# PSU.net
KiCad netlist of a schematic drawn in EAGLE
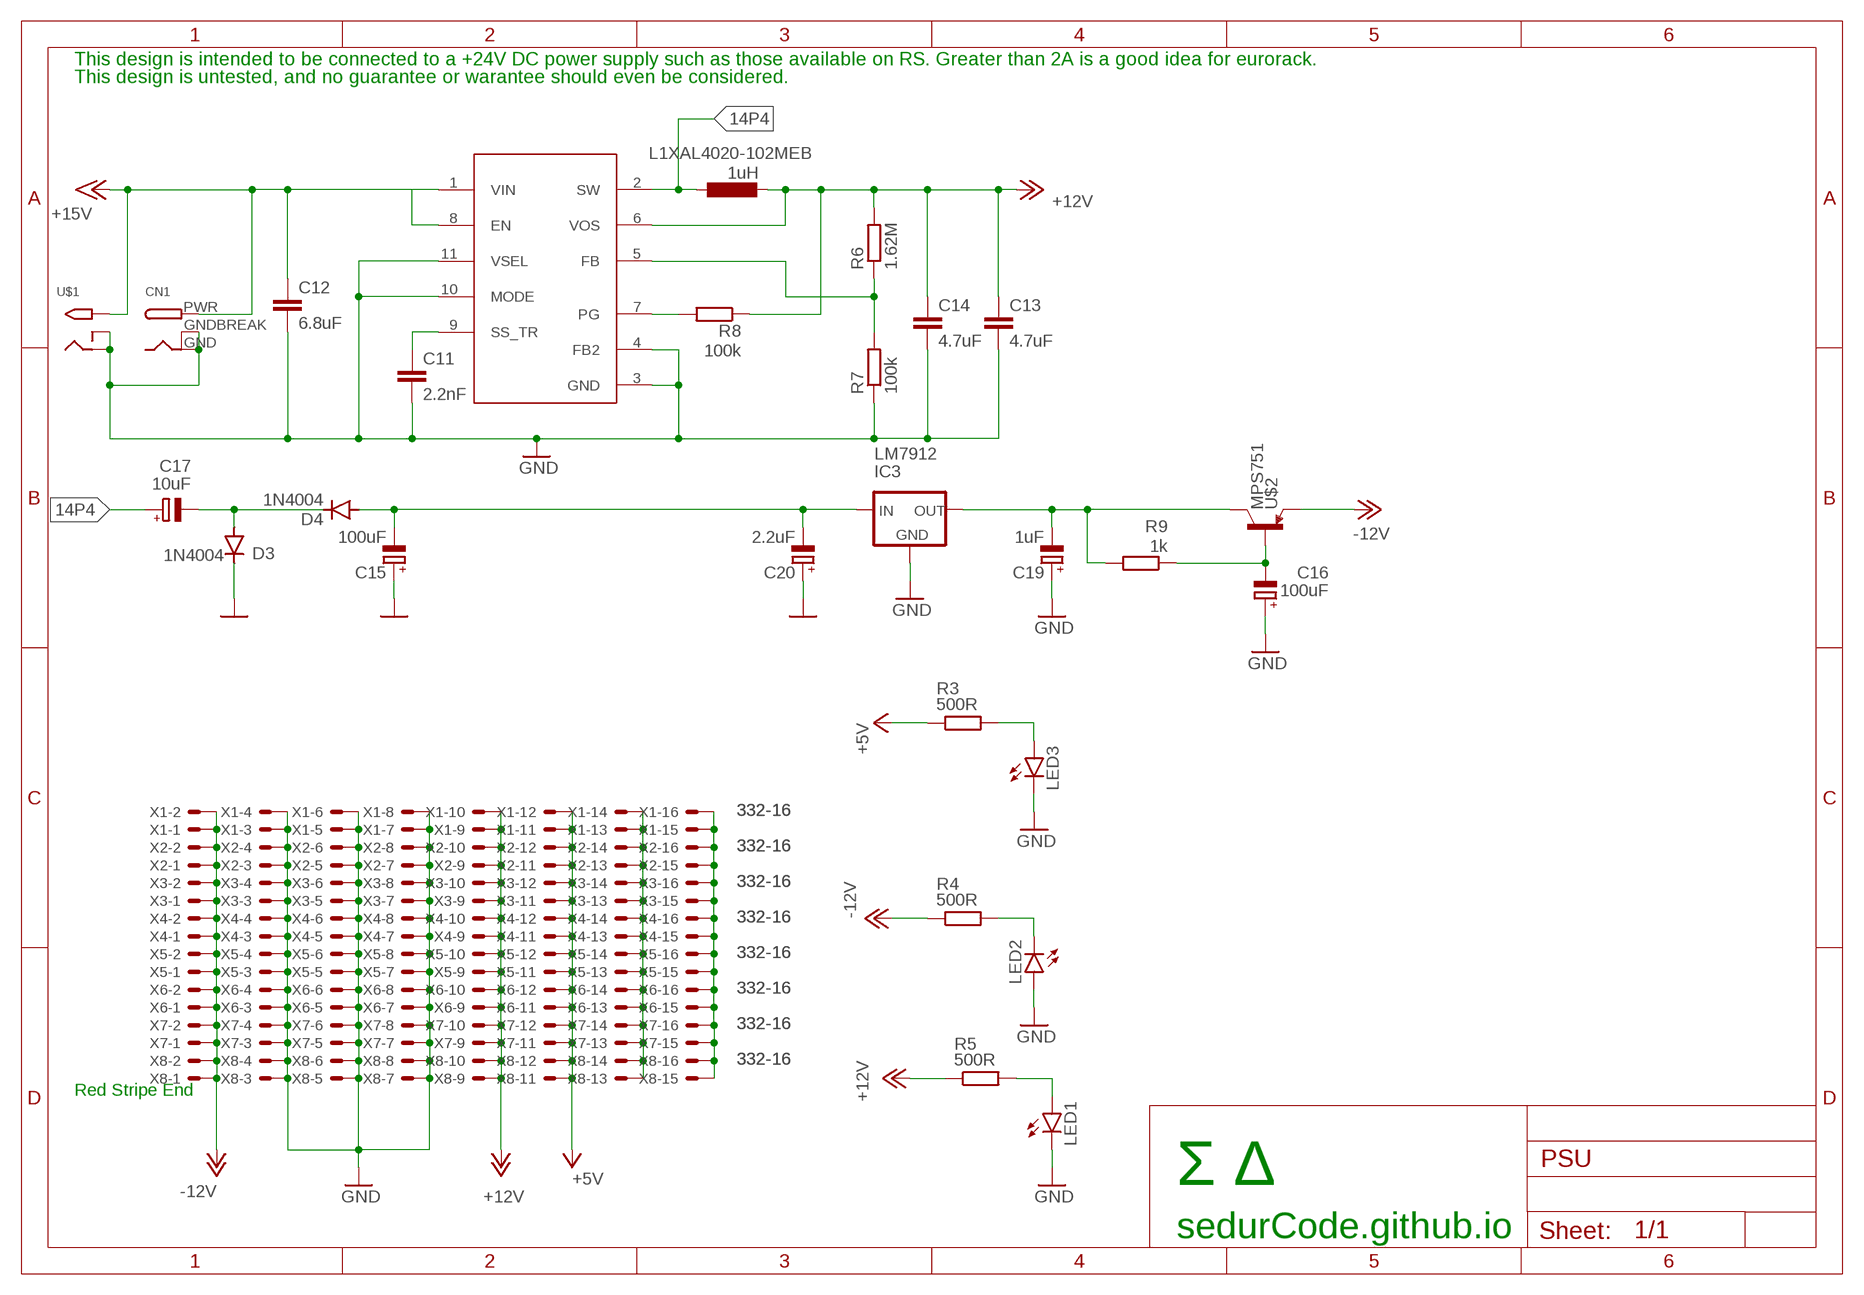
[diagram p0: schematic, sheet 1]

(export (version "E")
  (design (tool "Eeschema 10.0.6"))
  (components
    (comp (ref "C11")
      (value "2.2nF")
      (footprint "eagle-import:C0805")
      (libsource (lib "eagle-import") (part "C-EUC0805"))
    )
    (comp (ref "C12")
      (value "6.8uF")
      (footprint "eagle-import:C0805")
      (libsource (lib "eagle-import") (part "C-EUC0805"))
    )
    (comp (ref "C13")
      (value "4.7uF")
      (footprint "eagle-import:C0805")
      (libsource (lib "eagle-import") (part "C-EUC0805"))
    )
    (comp (ref "C14")
      (value "4.7uF")
      (footprint "eagle-import:C0805")
      (libsource (lib "eagle-import") (part "C-EUC0805"))
    )
    (comp (ref "C15")
      (value "100uF")
      (footprint "eagle-import:PANASONIC_B")
      (libsource (lib "eagle-import") (part "CPOL-EUB"))
    )
    (comp (ref "C16")
      (value "100uF")
      (footprint "eagle-import:PANASONIC_B")
      (libsource (lib "eagle-import") (part "CPOL-EUB"))
    )
    (comp (ref "C17")
      (value "10uF")
      (footprint "eagle-import:PANASONIC_B")
      (libsource (lib "eagle-import") (part "CPOL-EUB"))
    )
    (comp (ref "C19")
      (value "1uF")
      (footprint "eagle-import:PANASONIC_B")
      (libsource (lib "eagle-import") (part "CPOL-EUB"))
    )
    (comp (ref "C20")
      (value "2.2uF")
      (footprint "eagle-import:PANASONIC_B")
      (libsource (lib "eagle-import") (part "CPOL-EUB"))
    )
    (comp (ref "CN1")
      (value "DCBARRELPTH")
      (footprint "eagle-import:DCJACK_2MM_PTH")
      (fields (field (name "SPICEPREFIX") "X"))
      (libsource (lib "eagle-import") (part "DCBARRELPTH"))
    )
    (comp (ref "D3")
      (value "1N4004")
      (footprint "eagle-import:DO41-10")
      (libsource (lib "eagle-import") (part "1N4004"))
    )
    (comp (ref "D4")
      (value "1N4004")
      (footprint "eagle-import:DO41-10")
      (libsource (lib "eagle-import") (part "1N4004"))
    )
    (comp (ref "IC3")
      (value "LM7912")
      (footprint "eagle-import:79XXL")
      (fields (field (name "SPICEPREFIX") "J"))
      (libsource (lib "eagle-import") (part "79XXL"))
    )
    (comp (ref "L1XAL4020-102MEB")
      (value "1uH")
      (footprint "eagle-import:L5038P")
      (libsource (lib "eagle-import") (part "L-EUL5038P"))
    )
    (comp (ref "LED1")
      (value "LED5MM")
      (footprint "eagle-import:LED5MM")
      (libsource (lib "eagle-import") (part "LED5MM"))
    )
    (comp (ref "LED2")
      (value "LED5MM")
      (footprint "eagle-import:LED5MM")
      (libsource (lib "eagle-import") (part "LED5MM"))
    )
    (comp (ref "LED3")
      (value "LED5MM")
      (footprint "eagle-import:LED5MM")
      (libsource (lib "eagle-import") (part "LED5MM"))
    )
    (comp (ref "R3")
      (value "500R")
      (footprint "eagle-import:0207_7")
      (libsource (lib "eagle-import") (part "R-EU_0207/7"))
    )
    (comp (ref "R4")
      (value "500R")
      (footprint "eagle-import:0207_7")
      (libsource (lib "eagle-import") (part "R-EU_0207/7"))
    )
    (comp (ref "R5")
      (value "500R")
      (footprint "eagle-import:0207_7")
      (libsource (lib "eagle-import") (part "R-EU_0207/7"))
    )
    (comp (ref "R6")
      (value "1.62M")
      (footprint "eagle-import:R0805")
      (libsource (lib "eagle-import") (part "R-EU_R0805"))
    )
    (comp (ref "R7")
      (value "100k")
      (footprint "eagle-import:R0805")
      (libsource (lib "eagle-import") (part "R-EU_R0805"))
    )
    (comp (ref "R8")
      (value "100k")
      (footprint "eagle-import:R0805")
      (libsource (lib "eagle-import") (part "R-EU_R0805"))
    )
    (comp (ref "R9")
      (value "1k")
      (footprint "eagle-import:R0805")
      (libsource (lib "eagle-import") (part "R-EU_R0805"))
    )
    (comp (ref "U$1")
      (value "2.1MMJACKTHM")
      (footprint "eagle-import:PJ-102A")
      (libsource (lib "eagle-import") (part "2.1MMJACKTHM"))
    )
    (comp (ref "U$2")
      (value "MPS751")
      (footprint "eagle-import:TO92-EBC")
      (libsource (lib "eagle-import") (part "MPS751"))
    )
    (comp (ref "U2")
      (value "Value")
      (footprint "eagle-import:RGX0011A")
      (fields
        (field (name "MANUFACTURER") "Texas Instruments")
        (field (name "MANUFACTURER_PART_NUMBER") "TPS62135RGXR")
      )
      (libsource (lib "eagle-import") (part "TPS62135RGXR"))
    )
    (comp (ref "X1")
      (value "332-16")
      (footprint "eagle-import:332-16")
      (libsource (lib "eagle-import") (part "332-16"))
    )
    (comp (ref "X2")
      (value "332-16")
      (footprint "eagle-import:332-16")
      (libsource (lib "eagle-import") (part "332-16"))
    )
    (comp (ref "X3")
      (value "332-16")
      (footprint "eagle-import:332-16")
      (libsource (lib "eagle-import") (part "332-16"))
    )
    (comp (ref "X4")
      (value "332-16")
      (footprint "eagle-import:332-16")
      (libsource (lib "eagle-import") (part "332-16"))
    )
    (comp (ref "X5")
      (value "332-16")
      (footprint "eagle-import:332-16")
      (libsource (lib "eagle-import") (part "332-16"))
    )
    (comp (ref "X6")
      (value "332-16")
      (footprint "eagle-import:332-16")
      (libsource (lib "eagle-import") (part "332-16"))
    )
    (comp (ref "X7")
      (value "332-16")
      (footprint "eagle-import:332-16")
      (libsource (lib "eagle-import") (part "332-16"))
    )
    (comp (ref "X8")
      (value "332-16")
      (footprint "eagle-import:332-16")
      (libsource (lib "eagle-import") (part "332-16"))
    )
  )
  (nets
    (net (code "1") (name "+5V") (class "Default")
      (node (ref "R3") (pin "1") (pinfunction "1_1") (pintype "passive"))
      (node (ref "X1") (pin "11") (pinfunction "S_11") (pintype "passive"))
      (node (ref "X1") (pin "12") (pinfunction "S_12") (pintype "passive"))
      (node (ref "X2") (pin "11") (pinfunction "S_11") (pintype "passive"))
      (node (ref "X2") (pin "12") (pinfunction "S_12") (pintype "passive"))
      (node (ref "X3") (pin "11") (pinfunction "S_11") (pintype "passive"))
      (node (ref "X3") (pin "12") (pinfunction "S_12") (pintype "passive"))
      (node (ref "X4") (pin "11") (pinfunction "S_11") (pintype "passive"))
      (node (ref "X4") (pin "12") (pinfunction "S_12") (pintype "passive"))
      (node (ref "X5") (pin "11") (pinfunction "S_11") (pintype "passive"))
      (node (ref "X5") (pin "12") (pinfunction "S_12") (pintype "passive"))
      (node (ref "X6") (pin "11") (pinfunction "S_11") (pintype "passive"))
      (node (ref "X6") (pin "12") (pinfunction "S_12") (pintype "passive"))
      (node (ref "X7") (pin "11") (pinfunction "S_11") (pintype "passive"))
      (node (ref "X7") (pin "12") (pinfunction "S_12") (pintype "passive"))
      (node (ref "X8") (pin "11") (pinfunction "S_11") (pintype "passive"))
      (node (ref "X8") (pin "12") (pinfunction "S_12") (pintype "passive"))
    )
    (net (code "2") (name "+12V") (class "Default")
      (node (ref "C13") (pin "1") (pinfunction "1_1") (pintype "passive"))
      (node (ref "C14") (pin "1") (pinfunction "1_1") (pintype "passive"))
      (node (ref "L1XAL4020-102MEB") (pin "2") (pinfunction "2_2") (pintype "passive"))
      (node (ref "R5") (pin "1") (pinfunction "1_1") (pintype "passive"))
      (node (ref "R6") (pin "2") (pinfunction "2_2") (pintype "passive"))
      (node (ref "R8") (pin "1") (pinfunction "1_1") (pintype "passive"))
      (node (ref "U2") (pin "6") (pinfunction "VOS_6") (pintype "input"))
      (node (ref "X1") (pin "10") (pinfunction "S_10") (pintype "passive"))
      (node (ref "X1") (pin "9") (pinfunction "S_9") (pintype "passive"))
      (node (ref "X2") (pin "10") (pinfunction "S_10") (pintype "passive"))
      (node (ref "X2") (pin "9") (pinfunction "S_9") (pintype "passive"))
      (node (ref "X3") (pin "10") (pinfunction "S_10") (pintype "passive"))
      (node (ref "X3") (pin "9") (pinfunction "S_9") (pintype "passive"))
      (node (ref "X4") (pin "10") (pinfunction "S_10") (pintype "passive"))
      (node (ref "X4") (pin "9") (pinfunction "S_9") (pintype "passive"))
      (node (ref "X5") (pin "10") (pinfunction "S_10") (pintype "passive"))
      (node (ref "X5") (pin "9") (pinfunction "S_9") (pintype "passive"))
      (node (ref "X6") (pin "10") (pinfunction "S_10") (pintype "passive"))
      (node (ref "X6") (pin "9") (pinfunction "S_9") (pintype "passive"))
      (node (ref "X7") (pin "10") (pinfunction "S_10") (pintype "passive"))
      (node (ref "X7") (pin "9") (pinfunction "S_9") (pintype "passive"))
      (node (ref "X8") (pin "10") (pinfunction "S_10") (pintype "passive"))
      (node (ref "X8") (pin "9") (pinfunction "S_9") (pintype "passive"))
    )
    (net (code "3") (name "+15V") (class "Default")
      (node (ref "C12") (pin "1") (pinfunction "1_1") (pintype "passive"))
      (node (ref "CN1") (pin "PWR") (pinfunction "PWR_PWR") (pintype "power_in"))
      (node (ref "U$1") (pin "TIP") (pinfunction "TIP_TIP") (pintype "bidirectional"))
      (node (ref "U2") (pin "1") (pinfunction "VIN_1") (pintype "power_in"))
    )
    (net (code "4") (name "-12V") (class "Default")
      (node (ref "R4") (pin "1") (pinfunction "1_1") (pintype "passive"))
      (node (ref "U$2") (pin "E") (pinfunction "E_E") (pintype "passive"))
      (node (ref "X1") (pin "1") (pinfunction "S_1") (pintype "passive"))
      (node (ref "X1") (pin "2") (pinfunction "S_2") (pintype "passive"))
      (node (ref "X2") (pin "1") (pinfunction "S_1") (pintype "passive"))
      (node (ref "X2") (pin "2") (pinfunction "S_2") (pintype "passive"))
      (node (ref "X3") (pin "1") (pinfunction "S_1") (pintype "passive"))
      (node (ref "X3") (pin "2") (pinfunction "S_2") (pintype "passive"))
      (node (ref "X4") (pin "1") (pinfunction "S_1") (pintype "passive"))
      (node (ref "X4") (pin "2") (pinfunction "S_2") (pintype "passive"))
      (node (ref "X5") (pin "1") (pinfunction "S_1") (pintype "passive"))
      (node (ref "X5") (pin "2") (pinfunction "S_2") (pintype "passive"))
      (node (ref "X6") (pin "1") (pinfunction "S_1") (pintype "passive"))
      (node (ref "X6") (pin "2") (pinfunction "S_2") (pintype "passive"))
      (node (ref "X7") (pin "1") (pinfunction "S_1") (pintype "passive"))
      (node (ref "X7") (pin "2") (pinfunction "S_2") (pintype "passive"))
      (node (ref "X8") (pin "1") (pinfunction "S_1") (pintype "passive"))
      (node (ref "X8") (pin "2") (pinfunction "S_2") (pintype "passive"))
    )
    (net (code "5") (name "14P4") (class "Default")
      (node (ref "C17") (pin "+") (pinfunction "+_+") (pintype "passive"))
      (node (ref "L1XAL4020-102MEB") (pin "1") (pinfunction "1_1") (pintype "passive"))
      (node (ref "U2") (pin "2") (pinfunction "SW_2") (pintype "power_in"))
    )
    (net (code "6") (name "GND") (class "Default")
      (node (ref "C11") (pin "2") (pinfunction "2_2") (pintype "passive"))
      (node (ref "C12") (pin "2") (pinfunction "2_2") (pintype "passive"))
      (node (ref "C13") (pin "2") (pinfunction "2_2") (pintype "passive"))
      (node (ref "C14") (pin "2") (pinfunction "2_2") (pintype "passive"))
      (node (ref "C15") (pin "+") (pinfunction "+_+") (pintype "passive"))
      (node (ref "C16") (pin "+") (pinfunction "+_+") (pintype "passive"))
      (node (ref "C19") (pin "+") (pinfunction "+_+") (pintype "passive"))
      (node (ref "C20") (pin "+") (pinfunction "+_+") (pintype "passive"))
      (node (ref "CN1") (pin "GND") (pinfunction "GND_GND") (pintype "power_in"))
      (node (ref "CN1") (pin "GNDBREAK") (pinfunction "GNDBREAK_GNDBREAK") (pintype "power_in"))
      (node (ref "D3") (pin "C") (pinfunction "C_C") (pintype "passive"))
      (node (ref "IC3") (pin "GND") (pinfunction "GND_GND") (pintype "input"))
      (node (ref "LED1") (pin "K") (pinfunction "C_K") (pintype "passive"))
      (node (ref "LED2") (pin "A") (pinfunction "A_A") (pintype "passive"))
      (node (ref "LED3") (pin "K") (pinfunction "C_K") (pintype "passive"))
      (node (ref "R7") (pin "1") (pinfunction "1_1") (pintype "passive"))
      (node (ref "U$1") (pin "RING") (pinfunction "RING_RING") (pintype "bidirectional"))
      (node (ref "U$1") (pin "RING_SW") (pinfunction "RING_SW_RING_SW") (pintype "bidirectional"))
      (node (ref "U2") (pin "10") (pinfunction "MODE_10") (pintype "input"))
      (node (ref "U2") (pin "11") (pinfunction "VSEL_11") (pintype "input"))
      (node (ref "U2") (pin "3") (pinfunction "GND_3") (pintype "power_in"))
      (node (ref "U2") (pin "4") (pinfunction "FB2_4") (pintype "input"))
      (node (ref "X1") (pin "3") (pinfunction "S_3") (pintype "passive"))
      (node (ref "X1") (pin "4") (pinfunction "S_4") (pintype "passive"))
      (node (ref "X1") (pin "5") (pinfunction "S_5") (pintype "passive"))
      (node (ref "X1") (pin "6") (pinfunction "S_6") (pintype "passive"))
      (node (ref "X1") (pin "7") (pinfunction "S_7") (pintype "passive"))
      (node (ref "X1") (pin "8") (pinfunction "S_8") (pintype "passive"))
      (node (ref "X2") (pin "3") (pinfunction "S_3") (pintype "passive"))
      (node (ref "X2") (pin "4") (pinfunction "S_4") (pintype "passive"))
      (node (ref "X2") (pin "5") (pinfunction "S_5") (pintype "passive"))
      (node (ref "X2") (pin "6") (pinfunction "S_6") (pintype "passive"))
      (node (ref "X2") (pin "7") (pinfunction "S_7") (pintype "passive"))
      (node (ref "X2") (pin "8") (pinfunction "S_8") (pintype "passive"))
      (node (ref "X3") (pin "3") (pinfunction "S_3") (pintype "passive"))
      (node (ref "X3") (pin "4") (pinfunction "S_4") (pintype "passive"))
      (node (ref "X3") (pin "5") (pinfunction "S_5") (pintype "passive"))
      (node (ref "X3") (pin "6") (pinfunction "S_6") (pintype "passive"))
      (node (ref "X3") (pin "7") (pinfunction "S_7") (pintype "passive"))
      (node (ref "X3") (pin "8") (pinfunction "S_8") (pintype "passive"))
      (node (ref "X4") (pin "3") (pinfunction "S_3") (pintype "passive"))
      (node (ref "X4") (pin "4") (pinfunction "S_4") (pintype "passive"))
      (node (ref "X4") (pin "5") (pinfunction "S_5") (pintype "passive"))
      (node (ref "X4") (pin "6") (pinfunction "S_6") (pintype "passive"))
      (node (ref "X4") (pin "7") (pinfunction "S_7") (pintype "passive"))
      (node (ref "X4") (pin "8") (pinfunction "S_8") (pintype "passive"))
      (node (ref "X5") (pin "3") (pinfunction "S_3") (pintype "passive"))
      (node (ref "X5") (pin "4") (pinfunction "S_4") (pintype "passive"))
      (node (ref "X5") (pin "5") (pinfunction "S_5") (pintype "passive"))
      (node (ref "X5") (pin "6") (pinfunction "S_6") (pintype "passive"))
      (node (ref "X5") (pin "7") (pinfunction "S_7") (pintype "passive"))
      (node (ref "X5") (pin "8") (pinfunction "S_8") (pintype "passive"))
      (node (ref "X6") (pin "3") (pinfunction "S_3") (pintype "passive"))
      (node (ref "X6") (pin "4") (pinfunction "S_4") (pintype "passive"))
      (node (ref "X6") (pin "5") (pinfunction "S_5") (pintype "passive"))
      (node (ref "X6") (pin "6") (pinfunction "S_6") (pintype "passive"))
      (node (ref "X6") (pin "7") (pinfunction "S_7") (pintype "passive"))
      (node (ref "X6") (pin "8") (pinfunction "S_8") (pintype "passive"))
      (node (ref "X7") (pin "3") (pinfunction "S_3") (pintype "passive"))
      (node (ref "X7") (pin "4") (pinfunction "S_4") (pintype "passive"))
      (node (ref "X7") (pin "5") (pinfunction "S_5") (pintype "passive"))
      (node (ref "X7") (pin "6") (pinfunction "S_6") (pintype "passive"))
      (node (ref "X7") (pin "7") (pinfunction "S_7") (pintype "passive"))
      (node (ref "X7") (pin "8") (pinfunction "S_8") (pintype "passive"))
      (node (ref "X8") (pin "3") (pinfunction "S_3") (pintype "passive"))
      (node (ref "X8") (pin "4") (pinfunction "S_4") (pintype "passive"))
      (node (ref "X8") (pin "5") (pinfunction "S_5") (pintype "passive"))
      (node (ref "X8") (pin "6") (pinfunction "S_6") (pintype "passive"))
      (node (ref "X8") (pin "7") (pinfunction "S_7") (pintype "passive"))
      (node (ref "X8") (pin "8") (pinfunction "S_8") (pintype "passive"))
    )
    (net (code "7") (name "Net-(C15-Pad-)") (class "Default")
      (node (ref "C15") (pin "-") (pinfunction "-_-") (pintype "passive"))
      (node (ref "C20") (pin "-") (pinfunction "-_-") (pintype "passive"))
      (node (ref "D4") (pin "A") (pinfunction "A_A") (pintype "passive"))
      (node (ref "IC3") (pin "IN") (pinfunction "IN_IN") (pintype "input"))
    )
    (net (code "8") (name "Net-(C16-Pad-)") (class "Default")
      (node (ref "C16") (pin "-") (pinfunction "-_-") (pintype "passive"))
      (node (ref "R9") (pin "1") (pinfunction "1_1") (pintype "passive"))
      (node (ref "U$2") (pin "B") (pinfunction "B_B") (pintype "passive"))
    )
    (net (code "9") (name "Net-(C17-Pad-)") (class "Default")
      (node (ref "C17") (pin "-") (pinfunction "-_-") (pintype "passive"))
      (node (ref "D3") (pin "A") (pinfunction "A_A") (pintype "passive"))
      (node (ref "D4") (pin "C") (pinfunction "C_C") (pintype "passive"))
    )
    (net (code "10") (name "Net-(C19-Pad-)") (class "Default")
      (node (ref "C19") (pin "-") (pinfunction "-_-") (pintype "passive"))
      (node (ref "IC3") (pin "OUT") (pinfunction "OUT_OUT") (pintype "passive"))
      (node (ref "R9") (pin "2") (pinfunction "2_2") (pintype "passive"))
      (node (ref "U$2") (pin "C") (pinfunction "C_C") (pintype "passive"))
    )
    (net (code "11") (name "Net-(LED1-PadA)") (class "Default")
      (node (ref "LED1") (pin "A") (pinfunction "A_A") (pintype "passive"))
      (node (ref "R5") (pin "2") (pinfunction "2_2") (pintype "passive"))
    )
    (net (code "12") (name "Net-(LED2-C)") (class "Default")
      (node (ref "LED2") (pin "K") (pinfunction "C_K") (pintype "passive"))
      (node (ref "R4") (pin "2") (pinfunction "2_2") (pintype "passive"))
    )
    (net (code "13") (name "Net-(LED3-PadA)") (class "Default")
      (node (ref "LED3") (pin "A") (pinfunction "A_A") (pintype "passive"))
      (node (ref "R3") (pin "2") (pinfunction "2_2") (pintype "passive"))
    )
    (net (code "14") (name "Net-(U2-FB)") (class "Default")
      (node (ref "R6") (pin "1") (pinfunction "1_1") (pintype "passive"))
      (node (ref "R7") (pin "2") (pinfunction "2_2") (pintype "passive"))
      (node (ref "U2") (pin "5") (pinfunction "FB_5") (pintype "input"))
    )
    (net (code "15") (name "Net-(U2-PG)") (class "Default")
      (node (ref "R8") (pin "2") (pinfunction "2_2") (pintype "passive"))
      (node (ref "U2") (pin "7") (pinfunction "PG_7") (pintype "open_collector"))
    )
    (net (code "16") (name "Net-(U2-SS_TR)") (class "Default")
      (node (ref "C11") (pin "1") (pinfunction "1_1") (pintype "passive"))
      (node (ref "U2") (pin "9") (pinfunction "SS_TR_9") (pintype "input"))
    )
    (net (code "17") (name "Net-(X1E-S)") (class "Default")
      (node (ref "X1") (pin "13") (pinfunction "S_13") (pintype "passive"))
      (node (ref "X1") (pin "14") (pinfunction "S_14") (pintype "passive"))
      (node (ref "X2") (pin "13") (pinfunction "S_13") (pintype "passive"))
      (node (ref "X2") (pin "14") (pinfunction "S_14") (pintype "passive"))
      (node (ref "X3") (pin "13") (pinfunction "S_13") (pintype "passive"))
      (node (ref "X3") (pin "14") (pinfunction "S_14") (pintype "passive"))
      (node (ref "X4") (pin "13") (pinfunction "S_13") (pintype "passive"))
      (node (ref "X4") (pin "14") (pinfunction "S_14") (pintype "passive"))
      (node (ref "X5") (pin "13") (pinfunction "S_13") (pintype "passive"))
      (node (ref "X5") (pin "14") (pinfunction "S_14") (pintype "passive"))
      (node (ref "X6") (pin "13") (pinfunction "S_13") (pintype "passive"))
      (node (ref "X6") (pin "14") (pinfunction "S_14") (pintype "passive"))
      (node (ref "X7") (pin "13") (pinfunction "S_13") (pintype "passive"))
      (node (ref "X7") (pin "14") (pinfunction "S_14") (pintype "passive"))
      (node (ref "X8") (pin "13") (pinfunction "S_13") (pintype "passive"))
      (node (ref "X8") (pin "14") (pinfunction "S_14") (pintype "passive"))
    )
    (net (code "18") (name "Net-(X1G-S)") (class "Default")
      (node (ref "X1") (pin "15") (pinfunction "S_15") (pintype "passive"))
      (node (ref "X1") (pin "16") (pinfunction "S_16") (pintype "passive"))
      (node (ref "X2") (pin "15") (pinfunction "S_15") (pintype "passive"))
      (node (ref "X2") (pin "16") (pinfunction "S_16") (pintype "passive"))
      (node (ref "X3") (pin "15") (pinfunction "S_15") (pintype "passive"))
      (node (ref "X3") (pin "16") (pinfunction "S_16") (pintype "passive"))
      (node (ref "X4") (pin "15") (pinfunction "S_15") (pintype "passive"))
      (node (ref "X4") (pin "16") (pinfunction "S_16") (pintype "passive"))
      (node (ref "X5") (pin "15") (pinfunction "S_15") (pintype "passive"))
      (node (ref "X5") (pin "16") (pinfunction "S_16") (pintype "passive"))
      (node (ref "X6") (pin "15") (pinfunction "S_15") (pintype "passive"))
      (node (ref "X6") (pin "16") (pinfunction "S_16") (pintype "passive"))
      (node (ref "X7") (pin "15") (pinfunction "S_15") (pintype "passive"))
      (node (ref "X7") (pin "16") (pinfunction "S_16") (pintype "passive"))
      (node (ref "X8") (pin "15") (pinfunction "S_15") (pintype "passive"))
      (node (ref "X8") (pin "16") (pinfunction "S_16") (pintype "passive"))
    )
    (net (code "19") (name "unconnected-(U2-EN-Pad8)") (class "Default")
      (node (ref "U2") (pin "8") (pinfunction "EN_8") (pintype "input"))
    )
  )
)
